# GameboyCartridgeKS_RevengeLite.net
KiCad netlist of a schematic drawn in EAGLE
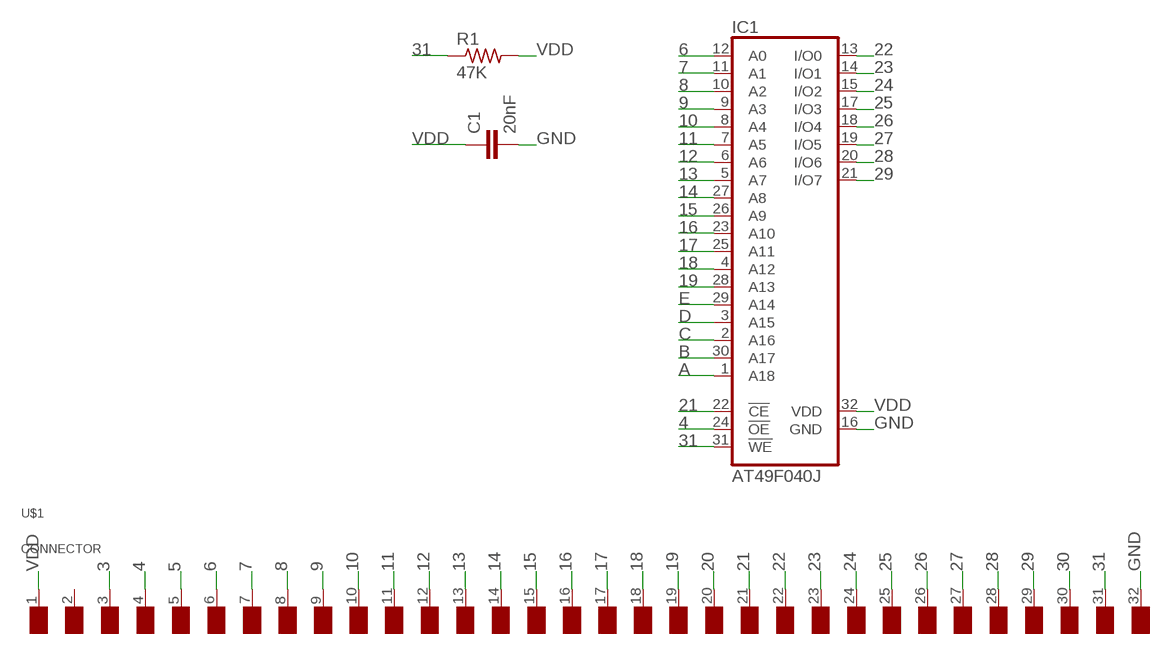
[diagram p0: schematic, sheet 1]

(export (version "E")
  (design (tool "Eeschema 10.0.6"))
  (components
    (comp (ref "C1")
      (value "20nF")
      (footprint "eagle-import:C0805")
      (libsource (lib "eagle-import") (part "C-EUC0805"))
    )
    (comp (ref "IC1")
      (value "AT49F040J")
      (footprint "eagle-import:PLCC32R")
      (libsource (lib "eagle-import") (part "AT49F040J"))
    )
    (comp (ref "R1")
      (value "47K")
      (footprint "eagle-import:M0805")
      (libsource (lib "eagle-import") (part "R-US_M0805"))
    )
    (comp (ref "U$1")
      (value "CONNECTOR")
      (footprint "eagle-import:CONNECTOR")
      (libsource (lib "eagle-import") (part "CONNECTOR"))
    )
  )
  (nets
    (net (code "1") (name "/3") (class "Default")
      (node (ref "U$1") (pin "3") (pinfunction "/WR_3") (pintype "bidirectional"))
    )
    (net (code "2") (name "/4") (class "Default")
      (node (ref "IC1") (pin "24") (pinfunction "~{OE}_24") (pintype "input"))
      (node (ref "U$1") (pin "4") (pinfunction "/RD_4") (pintype "bidirectional"))
    )
    (net (code "3") (name "/5") (class "Default")
      (node (ref "U$1") (pin "5") (pinfunction "/RCS_5") (pintype "bidirectional"))
    )
    (net (code "4") (name "/6") (class "Default")
      (node (ref "IC1") (pin "12") (pinfunction "A0_12") (pintype "input"))
      (node (ref "U$1") (pin "6") (pinfunction "A0_6") (pintype "bidirectional"))
    )
    (net (code "5") (name "/7") (class "Default")
      (node (ref "IC1") (pin "11") (pinfunction "A1_11") (pintype "input"))
      (node (ref "U$1") (pin "7") (pinfunction "A1_7") (pintype "bidirectional"))
    )
    (net (code "6") (name "/8") (class "Default")
      (node (ref "IC1") (pin "10") (pinfunction "A2_10") (pintype "input"))
      (node (ref "U$1") (pin "8") (pinfunction "A2_8") (pintype "bidirectional"))
    )
    (net (code "7") (name "/9") (class "Default")
      (node (ref "IC1") (pin "9") (pinfunction "A3_9") (pintype "input"))
      (node (ref "U$1") (pin "9") (pinfunction "A3_9") (pintype "bidirectional"))
    )
    (net (code "8") (name "/10") (class "Default")
      (node (ref "IC1") (pin "8") (pinfunction "A4_8") (pintype "input"))
      (node (ref "U$1") (pin "10") (pinfunction "A4_10") (pintype "bidirectional"))
    )
    (net (code "9") (name "/11") (class "Default")
      (node (ref "IC1") (pin "7") (pinfunction "A5_7") (pintype "input"))
      (node (ref "U$1") (pin "11") (pinfunction "A5_11") (pintype "bidirectional"))
    )
    (net (code "10") (name "/12") (class "Default")
      (node (ref "IC1") (pin "6") (pinfunction "A6_6") (pintype "input"))
      (node (ref "U$1") (pin "12") (pinfunction "A6_12") (pintype "bidirectional"))
    )
    (net (code "11") (name "/13") (class "Default")
      (node (ref "IC1") (pin "5") (pinfunction "A7_5") (pintype "input"))
      (node (ref "U$1") (pin "13") (pinfunction "A7_13") (pintype "bidirectional"))
    )
    (net (code "12") (name "/14") (class "Default")
      (node (ref "IC1") (pin "27") (pinfunction "A8_27") (pintype "input"))
      (node (ref "U$1") (pin "14") (pinfunction "A8_14") (pintype "bidirectional"))
    )
    (net (code "13") (name "/15") (class "Default")
      (node (ref "IC1") (pin "26") (pinfunction "A9_26") (pintype "input"))
      (node (ref "U$1") (pin "15") (pinfunction "A9_15") (pintype "bidirectional"))
    )
    (net (code "14") (name "/16") (class "Default")
      (node (ref "IC1") (pin "23") (pinfunction "A10_23") (pintype "input"))
      (node (ref "U$1") (pin "16") (pinfunction "A10_16") (pintype "bidirectional"))
    )
    (net (code "15") (name "/17") (class "Default")
      (node (ref "IC1") (pin "25") (pinfunction "A11_25") (pintype "input"))
      (node (ref "U$1") (pin "17") (pinfunction "A11_17") (pintype "bidirectional"))
    )
    (net (code "16") (name "/18") (class "Default")
      (node (ref "IC1") (pin "4") (pinfunction "A12_4") (pintype "input"))
      (node (ref "U$1") (pin "18") (pinfunction "A12_18") (pintype "bidirectional"))
    )
    (net (code "17") (name "/19") (class "Default")
      (node (ref "IC1") (pin "28") (pinfunction "A13_28") (pintype "input"))
      (node (ref "U$1") (pin "19") (pinfunction "A13_19") (pintype "bidirectional"))
    )
    (net (code "18") (name "/20") (class "Default")
      (node (ref "U$1") (pin "20") (pinfunction "A14_20") (pintype "bidirectional"))
    )
    (net (code "19") (name "/21") (class "Default")
      (node (ref "IC1") (pin "22") (pinfunction "~{CE}_22") (pintype "input"))
      (node (ref "U$1") (pin "21") (pinfunction "A15_21") (pintype "bidirectional"))
    )
    (net (code "20") (name "/22") (class "Default")
      (node (ref "IC1") (pin "13") (pinfunction "I/O0_13") (pintype "tri_state"))
      (node (ref "U$1") (pin "22") (pinfunction "D0_22") (pintype "bidirectional"))
    )
    (net (code "21") (name "/23") (class "Default")
      (node (ref "IC1") (pin "14") (pinfunction "I/O1_14") (pintype "tri_state"))
      (node (ref "U$1") (pin "23") (pinfunction "D1_23") (pintype "bidirectional"))
    )
    (net (code "22") (name "/24") (class "Default")
      (node (ref "IC1") (pin "15") (pinfunction "I/O2_15") (pintype "tri_state"))
      (node (ref "U$1") (pin "24") (pinfunction "D2_24") (pintype "bidirectional"))
    )
    (net (code "23") (name "/25") (class "Default")
      (node (ref "IC1") (pin "17") (pinfunction "I/O3_17") (pintype "tri_state"))
      (node (ref "U$1") (pin "25") (pinfunction "D3_25") (pintype "bidirectional"))
    )
    (net (code "24") (name "/26") (class "Default")
      (node (ref "IC1") (pin "18") (pinfunction "I/O4_18") (pintype "tri_state"))
      (node (ref "U$1") (pin "26") (pinfunction "D4_26") (pintype "bidirectional"))
    )
    (net (code "25") (name "/27") (class "Default")
      (node (ref "IC1") (pin "19") (pinfunction "I/O5_19") (pintype "tri_state"))
      (node (ref "U$1") (pin "27") (pinfunction "D5_27") (pintype "bidirectional"))
    )
    (net (code "26") (name "/28") (class "Default")
      (node (ref "IC1") (pin "20") (pinfunction "I/O6_20") (pintype "tri_state"))
      (node (ref "U$1") (pin "28") (pinfunction "D6_28") (pintype "bidirectional"))
    )
    (net (code "27") (name "/29") (class "Default")
      (node (ref "IC1") (pin "21") (pinfunction "I/O7_21") (pintype "tri_state"))
      (node (ref "U$1") (pin "29") (pinfunction "D7_29") (pintype "bidirectional"))
    )
    (net (code "28") (name "/30") (class "Default")
      (node (ref "U$1") (pin "30") (pinfunction "/RS_30") (pintype "bidirectional"))
    )
    (net (code "29") (name "/31") (class "Default")
      (node (ref "IC1") (pin "31") (pinfunction "~{WE}_31") (pintype "input"))
      (node (ref "R1") (pin "1") (pinfunction "1_1") (pintype "passive"))
      (node (ref "U$1") (pin "31") (pinfunction "VIN_31") (pintype "bidirectional"))
    )
    (net (code "30") (name "/A") (class "Default")
      (node (ref "IC1") (pin "1") (pinfunction "A18_1") (pintype "input"))
    )
    (net (code "31") (name "/B") (class "Default")
      (node (ref "IC1") (pin "30") (pinfunction "A17_30") (pintype "input"))
    )
    (net (code "32") (name "/C") (class "Default")
      (node (ref "IC1") (pin "2") (pinfunction "A16_2") (pintype "input"))
    )
    (net (code "33") (name "/D") (class "Default")
      (node (ref "IC1") (pin "3") (pinfunction "A15_3") (pintype "input"))
    )
    (net (code "34") (name "/E") (class "Default")
      (node (ref "IC1") (pin "29") (pinfunction "A14_29") (pintype "input"))
    )
    (net (code "35") (name "/GND") (class "Default")
      (node (ref "C1") (pin "2") (pinfunction "2_2") (pintype "passive"))
      (node (ref "IC1") (pin "16") (pinfunction "GND_16") (pintype "power_in"))
      (node (ref "U$1") (pin "32") (pinfunction "GND_32") (pintype "power_in"))
    )
    (net (code "36") (name "/VDD") (class "Default")
      (node (ref "C1") (pin "1") (pinfunction "1_1") (pintype "passive"))
      (node (ref "IC1") (pin "32") (pinfunction "VDD_32") (pintype "power_in"))
      (node (ref "R1") (pin "2") (pinfunction "2_2") (pintype "passive"))
      (node (ref "U$1") (pin "1") (pinfunction "VDD_1") (pintype "power_in"))
    )
    (net (code "37") (name "unconnected-(U$1-NC-Pad2)") (class "Default")
      (node (ref "U$1") (pin "2") (pinfunction "NC_2") (pintype "no_connect"))
    )
  )
)
